# emonTx4-ESP8266.net
KiCad netlist of a schematic drawn in EAGLE
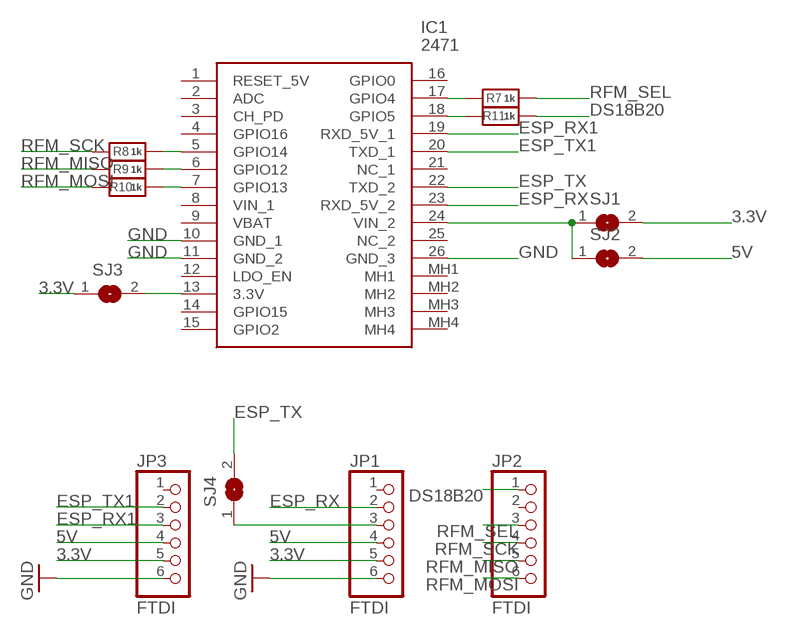
[diagram p0: schematic, sheet 1]

(export (version "E")
  (design (tool "Eeschema 10.0.6"))
  (components
    (comp (ref "IC1")
      (value "2471")
      (footprint "eagle-import:2471")
      (fields (field (name "MOUSER_PART_NUMBER") "485-2471"))
      (libsource (lib "eagle-import") (part "2471"))
    )
    (comp (ref "JP1")
      (value "FTDI")
      (footprint "eagle-import:1X06_ROUND_70")
      (libsource (lib "eagle-import") (part "HEADER-1X670MIL"))
    )
    (comp (ref "JP2")
      (value "FTDI")
      (footprint "eagle-import:1X06_ROUND_70")
      (libsource (lib "eagle-import") (part "HEADER-1X670MIL"))
    )
    (comp (ref "JP3")
      (value "FTDI")
      (footprint "eagle-import:1X06_ROUND_70")
      (libsource (lib "eagle-import") (part "HEADER-1X670MIL"))
    )
    (comp (ref "R7")
      (value "1k")
      (footprint "eagle-import:_0603")
      (libsource (lib "eagle-import") (part "RESISTOR_0603"))
    )
    (comp (ref "R8")
      (value "1k")
      (footprint "eagle-import:_0603")
      (libsource (lib "eagle-import") (part "RESISTOR_0603"))
    )
    (comp (ref "R9")
      (value "1k")
      (footprint "eagle-import:_0603")
      (libsource (lib "eagle-import") (part "RESISTOR_0603"))
    )
    (comp (ref "R10")
      (value "1k")
      (footprint "eagle-import:_0603")
      (libsource (lib "eagle-import") (part "RESISTOR_0603"))
    )
    (comp (ref "R11")
      (value "1k")
      (footprint "eagle-import:_0603")
      (libsource (lib "eagle-import") (part "RESISTOR_0603"))
    )
    (comp (ref "SJ1") (value "SJ") (footprint "eagle-import:SJ") (libsource (lib "eagle-import") (part "SJ")))
    (comp (ref "SJ2") (value "SJ") (footprint "eagle-import:SJ") (libsource (lib "eagle-import") (part "SJ")))
    (comp (ref "SJ3") (value "SJ") (footprint "eagle-import:SJ") (libsource (lib "eagle-import") (part "SJ")))
    (comp (ref "SJ4") (value "SJ") (footprint "eagle-import:SJ") (libsource (lib "eagle-import") (part "SJ")))
  )
  (nets
    (net (code "1") (name "/3.3V") (class "Default")
      (node (ref "JP1") (pin "5") (pinfunction "5_5") (pintype "passive"))
      (node (ref "JP3") (pin "5") (pinfunction "5_5") (pintype "passive"))
      (node (ref "SJ1") (pin "2") (pinfunction "2_2") (pintype "passive"))
      (node (ref "SJ3") (pin "1") (pinfunction "1_1") (pintype "passive"))
    )
    (net (code "2") (name "/5V") (class "Default")
      (node (ref "JP1") (pin "4") (pinfunction "4_4") (pintype "passive"))
      (node (ref "JP3") (pin "4") (pinfunction "4_4") (pintype "passive"))
      (node (ref "SJ2") (pin "2") (pinfunction "2_2") (pintype "passive"))
    )
    (net (code "3") (name "/DS18B20") (class "Default")
      (node (ref "JP2") (pin "1") (pinfunction "1_1") (pintype "passive"))
      (node (ref "R11") (pin "1") (pinfunction "1_1") (pintype "passive"))
    )
    (net (code "4") (name "/ESP_RX") (class "Default")
      (node (ref "IC1") (pin "23") (pinfunction "RXD_5V_2_23") (pintype "bidirectional"))
      (node (ref "JP1") (pin "2") (pinfunction "2_2") (pintype "passive"))
    )
    (net (code "5") (name "/ESP_RX1") (class "Default")
      (node (ref "IC1") (pin "19") (pinfunction "RXD_5V_1_19") (pintype "bidirectional"))
      (node (ref "JP3") (pin "3") (pinfunction "3_3") (pintype "passive"))
    )
    (net (code "6") (name "/ESP_TX") (class "Default")
      (node (ref "IC1") (pin "22") (pinfunction "TXD_2_22") (pintype "bidirectional"))
      (node (ref "SJ4") (pin "2") (pinfunction "2_2") (pintype "passive"))
    )
    (net (code "7") (name "/ESP_TX1") (class "Default")
      (node (ref "IC1") (pin "20") (pinfunction "TXD_1_20") (pintype "bidirectional"))
      (node (ref "JP3") (pin "2") (pinfunction "2_2") (pintype "passive"))
    )
    (net (code "8") (name "/RFM_MISO") (class "Default")
      (node (ref "JP2") (pin "5") (pinfunction "5_5") (pintype "passive"))
      (node (ref "R9") (pin "2") (pinfunction "2_2") (pintype "passive"))
    )
    (net (code "9") (name "/RFM_MOSI") (class "Default")
      (node (ref "JP2") (pin "6") (pinfunction "6_6") (pintype "passive"))
      (node (ref "R10") (pin "2") (pinfunction "2_2") (pintype "passive"))
    )
    (net (code "10") (name "/RFM_SCK") (class "Default")
      (node (ref "JP2") (pin "4") (pinfunction "4_4") (pintype "passive"))
      (node (ref "R8") (pin "2") (pinfunction "2_2") (pintype "passive"))
    )
    (net (code "11") (name "/RFM_SEL") (class "Default")
      (node (ref "JP2") (pin "3") (pinfunction "3_3") (pintype "passive"))
      (node (ref "R7") (pin "1") (pinfunction "1_1") (pintype "passive"))
    )
    (net (code "12") (name "GND") (class "Default")
      (node (ref "IC1") (pin "10") (pinfunction "GND_1_10") (pintype "bidirectional"))
      (node (ref "IC1") (pin "11") (pinfunction "GND_2_11") (pintype "bidirectional"))
      (node (ref "IC1") (pin "26") (pinfunction "GND_3_26") (pintype "bidirectional"))
      (node (ref "JP1") (pin "6") (pinfunction "6_6") (pintype "passive"))
      (node (ref "JP3") (pin "6") (pinfunction "6_6") (pintype "passive"))
    )
    (net (code "13") (name "Net-(IC1-3.3V)") (class "Default")
      (node (ref "IC1") (pin "13") (pinfunction "3.3V_13") (pintype "bidirectional"))
      (node (ref "SJ3") (pin "2") (pinfunction "2_2") (pintype "passive"))
    )
    (net (code "14") (name "Net-(IC1-GPIO4)") (class "Default")
      (node (ref "IC1") (pin "17") (pinfunction "GPIO4_17") (pintype "bidirectional"))
      (node (ref "R7") (pin "2") (pinfunction "2_2") (pintype "passive"))
    )
    (net (code "15") (name "Net-(IC1-GPIO5)") (class "Default")
      (node (ref "IC1") (pin "18") (pinfunction "GPIO5_18") (pintype "bidirectional"))
      (node (ref "R11") (pin "2") (pinfunction "2_2") (pintype "passive"))
    )
    (net (code "16") (name "Net-(IC1-GPIO12)") (class "Default")
      (node (ref "IC1") (pin "6") (pinfunction "GPIO12_6") (pintype "bidirectional"))
      (node (ref "R9") (pin "1") (pinfunction "1_1") (pintype "passive"))
    )
    (net (code "17") (name "Net-(IC1-GPIO13)") (class "Default")
      (node (ref "IC1") (pin "7") (pinfunction "GPIO13_7") (pintype "bidirectional"))
      (node (ref "R10") (pin "1") (pinfunction "1_1") (pintype "passive"))
    )
    (net (code "18") (name "Net-(IC1-GPIO14)") (class "Default")
      (node (ref "IC1") (pin "5") (pinfunction "GPIO14_5") (pintype "bidirectional"))
      (node (ref "R8") (pin "1") (pinfunction "1_1") (pintype "passive"))
    )
    (net (code "19") (name "Net-(IC1-VIN_2)") (class "Default")
      (node (ref "IC1") (pin "24") (pinfunction "VIN_2_24") (pintype "bidirectional"))
      (node (ref "SJ1") (pin "1") (pinfunction "1_1") (pintype "passive"))
      (node (ref "SJ2") (pin "1") (pinfunction "1_1") (pintype "passive"))
    )
    (net (code "20") (name "Net-(JP1-Pad3)") (class "Default")
      (node (ref "JP1") (pin "3") (pinfunction "3_3") (pintype "passive"))
      (node (ref "SJ4") (pin "1") (pinfunction "1_1") (pintype "passive"))
    )
    (net (code "21") (name "unconnected-(IC1-ADC-Pad2)") (class "Default")
      (node (ref "IC1") (pin "2") (pinfunction "ADC_2") (pintype "bidirectional"))
    )
    (net (code "22") (name "unconnected-(IC1-CH_PD-Pad3)") (class "Default")
      (node (ref "IC1") (pin "3") (pinfunction "CH_PD_3") (pintype "bidirectional"))
    )
    (net (code "23") (name "unconnected-(IC1-GPIO0-Pad16)") (class "Default")
      (node (ref "IC1") (pin "16") (pinfunction "GPIO0_16") (pintype "bidirectional"))
    )
    (net (code "24") (name "unconnected-(IC1-GPIO2-Pad15)") (class "Default")
      (node (ref "IC1") (pin "15") (pinfunction "GPIO2_15") (pintype "bidirectional"))
    )
    (net (code "25") (name "unconnected-(IC1-GPIO15-Pad14)") (class "Default")
      (node (ref "IC1") (pin "14") (pinfunction "GPIO15_14") (pintype "bidirectional"))
    )
    (net (code "26") (name "unconnected-(IC1-GPIO16-Pad4)") (class "Default")
      (node (ref "IC1") (pin "4") (pinfunction "GPIO16_4") (pintype "bidirectional"))
    )
    (net (code "27") (name "unconnected-(IC1-LDO_EN-Pad12)") (class "Default")
      (node (ref "IC1") (pin "12") (pinfunction "LDO_EN_12") (pintype "bidirectional"))
    )
    (net (code "28") (name "unconnected-(IC1-NC_1-Pad21)") (class "Default")
      (node (ref "IC1") (pin "21") (pinfunction "NC_1_21") (pintype "bidirectional"))
    )
    (net (code "29") (name "unconnected-(IC1-NC_2-Pad25)") (class "Default")
      (node (ref "IC1") (pin "25") (pinfunction "NC_2_25") (pintype "bidirectional"))
    )
    (net (code "30") (name "unconnected-(IC1-PadMH1)") (class "Default")
      (node (ref "IC1") (pin "MH1") (pinfunction "MH1_MH1") (pintype "bidirectional"))
    )
    (net (code "31") (name "unconnected-(IC1-PadMH2)") (class "Default")
      (node (ref "IC1") (pin "MH2") (pinfunction "MH2_MH2") (pintype "bidirectional"))
    )
    (net (code "32") (name "unconnected-(IC1-PadMH3)") (class "Default")
      (node (ref "IC1") (pin "MH3") (pinfunction "MH3_MH3") (pintype "bidirectional"))
    )
    (net (code "33") (name "unconnected-(IC1-PadMH4)") (class "Default")
      (node (ref "IC1") (pin "MH4") (pinfunction "MH4_MH4") (pintype "bidirectional"))
    )
    (net (code "34") (name "unconnected-(IC1-RESET_5V-Pad1)") (class "Default")
      (node (ref "IC1") (pin "1") (pinfunction "RESET_5V_1") (pintype "bidirectional"))
    )
    (net (code "35") (name "unconnected-(IC1-VBAT-Pad9)") (class "Default")
      (node (ref "IC1") (pin "9") (pinfunction "VBAT_9") (pintype "bidirectional"))
    )
    (net (code "36") (name "unconnected-(IC1-VIN_1-Pad8)") (class "Default")
      (node (ref "IC1") (pin "8") (pinfunction "VIN_1_8") (pintype "bidirectional"))
    )
    (net (code "37") (name "unconnected-(JP1-Pad1)") (class "Default")
      (node (ref "JP1") (pin "1") (pinfunction "1_1") (pintype "passive"))
    )
    (net (code "38") (name "unconnected-(JP2-Pad2)") (class "Default")
      (node (ref "JP2") (pin "2") (pinfunction "2_2") (pintype "passive"))
    )
    (net (code "39") (name "unconnected-(JP3-Pad1)") (class "Default")
      (node (ref "JP3") (pin "1") (pinfunction "1_1") (pintype "passive"))
    )
  )
)
